# P01-Power.net
KiCad netlist of a schematic drawn in Altium Designer
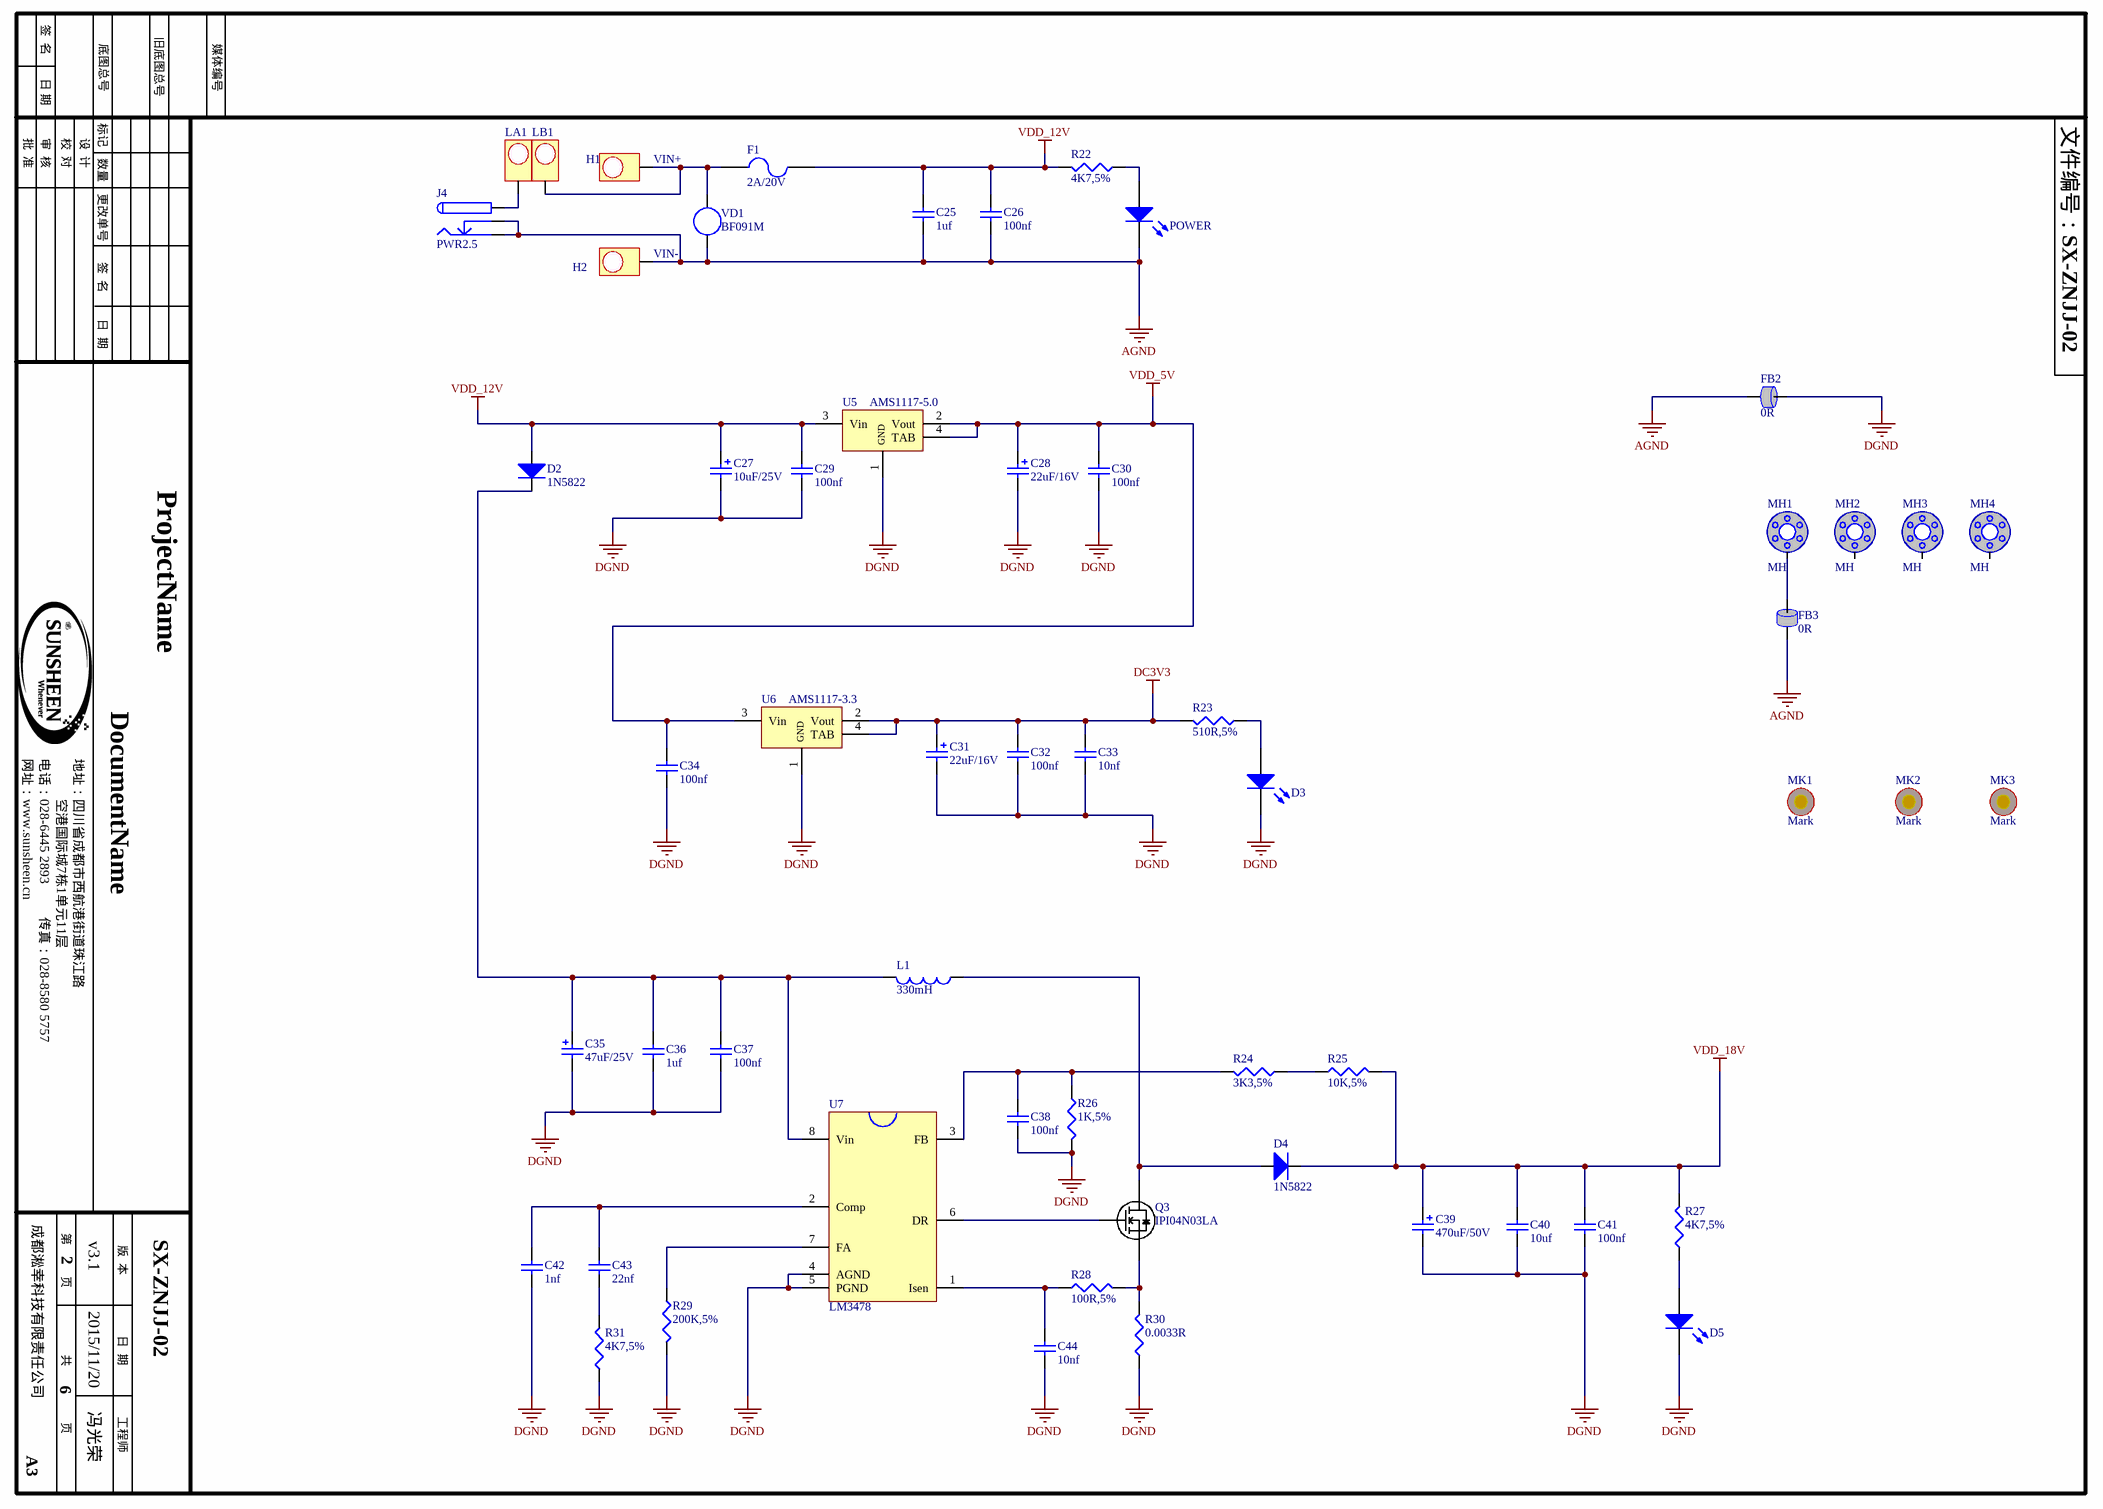
[diagram p0: P01-Power.SchDoc]

(export (version "E")
  (design (tool "Eeschema 10.0.6"))
  (components
    (comp (ref "C25")
      (value "1uf")
      (footprint "Cap0603")
      (description "无极性电容（表贴）")
      (libsource (lib "MyAD_Library") (part "Cap Semi"))
    )
    (comp (ref "C26")
      (value "100nf")
      (footprint "Cap0603")
      (description "无极性电容（表贴）")
      (libsource (lib "MyAD_Library") (part "Cap Semi"))
    )
    (comp (ref "C27")
      (value "10uF/25V")
      (footprint "CapPol1_D5")
      (description "极性电容（径向）")
      (libsource (lib "MyAD_Library") (part "Cap Pol1"))
    )
    (comp (ref "C28")
      (value "22uF/16V")
      (footprint "CapPol1_D5")
      (description "极性电容（径向）")
      (libsource (lib "MyAD_Library") (part "Cap Pol1"))
    )
    (comp (ref "C29")
      (value "100nf")
      (footprint "Cap0603")
      (description "无极性电容（表贴）")
      (libsource (lib "MyAD_Library") (part "Cap Semi"))
    )
    (comp (ref "C30")
      (value "100nf")
      (footprint "Cap0603")
      (description "无极性电容（表贴）")
      (libsource (lib "MyAD_Library") (part "Cap Semi"))
    )
    (comp (ref "C31")
      (value "22uF/16V")
      (footprint "CapPol1_D5")
      (description "极性电容（径向）")
      (libsource (lib "MyAD_Library") (part "Cap Pol1"))
    )
    (comp (ref "C32")
      (value "100nf")
      (footprint "Cap0603")
      (description "无极性电容（表贴）")
      (libsource (lib "MyAD_Library") (part "Cap Semi"))
    )
    (comp (ref "C33")
      (value "10nf")
      (footprint "Cap0603")
      (description "无极性电容（表贴）")
      (libsource (lib "MyAD_Library") (part "Cap Semi"))
    )
    (comp (ref "C34")
      (value "100nf")
      (footprint "Cap0603")
      (description "无极性电容（表贴）")
      (libsource (lib "MyAD_Library") (part "Cap Semi"))
    )
    (comp (ref "C35")
      (value "47uF/25V")
      (footprint "CapPol1_D6")
      (description "极性电容（径向）")
      (libsource (lib "MyAD_Library") (part "Cap Pol1"))
    )
    (comp (ref "C36")
      (value "1uf")
      (footprint "Cap0603")
      (description "无极性电容（表贴）")
      (libsource (lib "MyAD_Library") (part "Cap Semi"))
    )
    (comp (ref "C37")
      (value "100nf")
      (footprint "Cap0603")
      (description "无极性电容（表贴）")
      (libsource (lib "MyAD_Library") (part "Cap Semi"))
    )
    (comp (ref "C38")
      (value "100nf")
      (footprint "Cap0603")
      (description "无极性电容（表贴）")
      (libsource (lib "MyAD_Library") (part "Cap Semi"))
    )
    (comp (ref "C39")
      (value "470uF/50V")
      (footprint "CapPol1_D10")
      (description "极性电容（径向）")
      (libsource (lib "MyAD_Library") (part "Cap Pol1"))
    )
    (comp (ref "C40")
      (value "10uf")
      (footprint "Cap0603")
      (description "无极性电容（表贴）")
      (libsource (lib "MyAD_Library") (part "Cap Semi"))
    )
    (comp (ref "C41")
      (value "100nf")
      (footprint "Cap0603")
      (description "无极性电容（表贴）")
      (libsource (lib "MyAD_Library") (part "Cap Semi"))
    )
    (comp (ref "C42")
      (value "1nf")
      (footprint "Cap0603")
      (description "无极性电容（表贴）")
      (libsource (lib "MyAD_Library") (part "Cap Semi"))
    )
    (comp (ref "C43")
      (value "22nf")
      (footprint "Cap0603")
      (description "无极性电容（表贴）")
      (libsource (lib "MyAD_Library") (part "Cap Semi"))
    )
    (comp (ref "C44")
      (value "10nf")
      (footprint "Cap0603")
      (description "无极性电容（表贴）")
      (libsource (lib "MyAD_Library") (part "Cap Semi"))
    )
    (comp (ref "D2")
      (value "1N5822")
      (footprint "1N5822")
      (description "肖基特二极管")
      (libsource (lib "Schlib1") (part "DIODE"))
    )
    (comp (ref "D3")
      (value "RED")
      (footprint "LED0603")
      (description "Typical RED, GREEN, YELLOW, AMBER GaAs LED")
      (libsource (lib "MyAD_Library") (part "LED"))
    )
    (comp (ref "D4")
      (value "1N5822")
      (footprint "1N5822")
      (description "肖基特二极管")
      (libsource (lib "Schlib1") (part "DIODE"))
    )
    (comp (ref "D5")
      (value "RED")
      (footprint "LED0603")
      (description "Typical RED, GREEN, YELLOW, AMBER GaAs LED")
      (libsource (lib "MyAD_Library") (part "LED"))
    )
    (comp (ref "F1")
      (value "2A/20V")
      (footprint "1812")
      (description "保险丝")
      (libsource (lib "MyAD_Library") (part "Fuse"))
    )
    (comp (ref "FB2")
      (value "0R")
      (footprint "FB0603")
      (description "磁珠")
      (libsource (lib "MyAD_Library") (part "FerriteBead"))
    )
    (comp (ref "FB3")
      (value "0R")
      (footprint "FB0603")
      (description "磁珠")
      (libsource (lib "") (part "FerriteBead_1"))
    )
    (comp (ref "H1")
      (value "VIN+")
      (footprint "HOLE_POWER")
      (description "电源接线孔")
      (libsource (lib "") (part "HOLE_POWER_1"))
    )
    (comp (ref "H2")
      (value "VIN-")
      (footprint "HOLE_POWER")
      (description "电源接线孔")
      (libsource (lib "") (part "HOLE_POWER_1"))
    )
    (comp (ref "J4")
      (value "PWR2.5")
      (footprint "KLD-0202")
      (description "低电压电源连接器")
      (libsource (lib "MyAD_Library") (part "PWR2.5"))
    )
    (comp (ref "L1")
      (value "330mH")
      (footprint "Inductor_12x12x7")
      (description "电感")
      (libsource (lib "Schlib1") (part "Inductor"))
    )
    (comp (ref "LA1")
      (value "HOLE_POWER")
      (footprint "HOLE_POWER")
      (description "电源接线孔")
      (libsource (lib "MyAD_Library") (part "HOLE_POWER"))
    )
    (comp (ref "LB1")
      (value "HOLE_POWER")
      (footprint "HOLE_POWER")
      (description "电源接线孔")
      (libsource (lib "MyAD_Library") (part "HOLE_POWER"))
    )
    (comp (ref "MH1")
      (value "MH")
      (footprint "AS_D3mm-6mm")
      (description "固定孔")
      (libsource (lib "MyAD_Library") (part "MH"))
    )
    (comp (ref "MH2")
      (value "MH")
      (footprint "AS_D3mm-6mm")
      (description "固定孔")
      (libsource (lib "MyAD_Library") (part "MH"))
    )
    (comp (ref "MH3")
      (value "MH")
      (footprint "AS_D3mm-6mm")
      (description "固定孔")
      (libsource (lib "MyAD_Library") (part "MH"))
    )
    (comp (ref "MH4")
      (value "MH")
      (footprint "AS_D3mm-6mm")
      (description "固定孔")
      (libsource (lib "MyAD_Library") (part "MH"))
    )
    (comp (ref "MK1")
      (value "Mark")
      (footprint "MK")
      (description "贴片马克点")
      (libsource (lib "MyAD_Library") (part "Mark"))
    )
    (comp (ref "MK2")
      (value "Mark")
      (footprint "MK")
      (description "贴片马克点")
      (libsource (lib "MyAD_Library") (part "Mark"))
    )
    (comp (ref "MK3")
      (value "Mark")
      (footprint "MK")
      (description "贴片马克点")
      (libsource (lib "MyAD_Library") (part "Mark"))
    )
    (comp (ref "POWER")
      (value "RED")
      (footprint "LED0603")
      (description "Typical RED, GREEN, YELLOW, AMBER GaAs LED")
      (libsource (lib "MyAD_Library") (part "LED"))
    )
    (comp (ref "Q3")
      (value "IPI04N03LA")
      (footprint "TO228")
      (description "N沟道MOS管")
      (libsource (lib "Schlib1") (part "IPI04N03LA"))
    )
    (comp (ref "R22")
      (value "4K7,5%")
      (footprint "Res0603")
      (description "电阻")
      (libsource (lib "MyAD_Library") (part "Res"))
    )
    (comp (ref "R23")
      (value "510R,5%")
      (footprint "Res0603")
      (description "电阻")
      (libsource (lib "MyAD_Library") (part "Res"))
    )
    (comp (ref "R24")
      (value "3K3,5%")
      (footprint "Res0603")
      (description "电阻")
      (libsource (lib "MyAD_Library") (part "Res"))
    )
    (comp (ref "R25")
      (value "10K,5%")
      (footprint "Res0603")
      (description "电阻")
      (libsource (lib "MyAD_Library") (part "Res"))
    )
    (comp (ref "R26")
      (value "1K,5%")
      (footprint "Res0603")
      (description "电阻")
      (libsource (lib "MyAD_Library") (part "Res"))
    )
    (comp (ref "R27")
      (value "4K7,5%")
      (footprint "Res0603")
      (description "电阻")
      (libsource (lib "MyAD_Library") (part "Res"))
    )
    (comp (ref "R28")
      (value "100R,5%")
      (footprint "Res0603")
      (description "电阻")
      (libsource (lib "MyAD_Library") (part "Res"))
    )
    (comp (ref "R29")
      (value "200K,5%")
      (footprint "Res0603")
      (description "电阻")
      (libsource (lib "MyAD_Library") (part "Res"))
    )
    (comp (ref "R30")
      (value "0.0033R")
      (footprint "1206A")
      (description "电阻")
      (libsource (lib "MyAD_Library") (part "Res"))
    )
    (comp (ref "R31")
      (value "4K7,5%")
      (footprint "Res0603")
      (description "电阻")
      (libsource (lib "MyAD_Library") (part "Res"))
    )
    (comp (ref "U5")
      (value "AMS1117-5.0")
      (footprint "AMS1117")
      (description "稳压器")
      (libsource (lib "MyAD_Library") (part "AMS1117-3.3"))
    )
    (comp (ref "U6")
      (value "AMS1117-3.3")
      (footprint "AMS1117")
      (description "稳压器")
      (libsource (lib "MyAD_Library") (part "AMS1117-3.3"))
    )
    (comp (ref "U7")
      (value "LM3478")
      (footprint "SOP65P490X110-8N")
      (libsource (lib "Schlib1") (part "LM3478"))
    )
    (comp (ref "VD1") (value "BF091M") (footprint "B3D230L") (libsource (lib "Schlib1") (part "B3D230L")))
  )
  (nets
    (net (code "1") (name "AGND") (class "Default")
      (node (ref "C25") (pin "1") (pinfunction "1_1") (pintype "passive"))
      (node (ref "C26") (pin "1") (pinfunction "1_1") (pintype "passive"))
      (node (ref "FB2") (pin "1") (pinfunction "1_1") (pintype "passive"))
      (node (ref "FB3") (pin "1") (pinfunction "1_1") (pintype "passive"))
      (node (ref "H2") (pin "1") (pinfunction "1_1") (pintype "passive"))
      (node (ref "J4") (pin "2") (pinfunction "2_2") (pintype "power_in"))
      (node (ref "J4") (pin "3") (pinfunction "3_3") (pintype "power_in"))
      (node (ref "POWER") (pin "K") (pinfunction "K_K") (pintype "passive"))
      (node (ref "VD1") (pin "2") (pinfunction "2_2") (pintype "passive"))
    )
    (net (code "2") (name "DC3V3") (class "Default")
      (node (ref "C31") (pin "1") (pinfunction "1_1") (pintype "passive"))
      (node (ref "C32") (pin "2") (pinfunction "2_2") (pintype "passive"))
      (node (ref "C33") (pin "2") (pinfunction "2_2") (pintype "passive"))
      (node (ref "R23") (pin "2") (pinfunction "2_2") (pintype "passive"))
      (node (ref "U6") (pin "2") (pinfunction "Vout_2") (pintype "passive"))
      (node (ref "U6") (pin "4") (pinfunction "TAB_4") (pintype "passive"))
    )
    (net (code "3") (name "DGND") (class "Default")
      (node (ref "C27") (pin "2") (pinfunction "2_2") (pintype "passive"))
      (node (ref "C28") (pin "2") (pinfunction "2_2") (pintype "passive"))
      (node (ref "C29") (pin "1") (pinfunction "1_1") (pintype "passive"))
      (node (ref "C30") (pin "1") (pinfunction "1_1") (pintype "passive"))
      (node (ref "C31") (pin "2") (pinfunction "2_2") (pintype "passive"))
      (node (ref "C32") (pin "1") (pinfunction "1_1") (pintype "passive"))
      (node (ref "C33") (pin "1") (pinfunction "1_1") (pintype "passive"))
      (node (ref "C34") (pin "1") (pinfunction "1_1") (pintype "passive"))
      (node (ref "C35") (pin "2") (pinfunction "2_2") (pintype "passive"))
      (node (ref "C36") (pin "1") (pinfunction "1_1") (pintype "passive"))
      (node (ref "C37") (pin "1") (pinfunction "1_1") (pintype "passive"))
      (node (ref "C38") (pin "1") (pinfunction "1_1") (pintype "passive"))
      (node (ref "C39") (pin "2") (pinfunction "2_2") (pintype "passive"))
      (node (ref "C40") (pin "1") (pinfunction "1_1") (pintype "passive"))
      (node (ref "C41") (pin "1") (pinfunction "1_1") (pintype "passive"))
      (node (ref "C42") (pin "1") (pinfunction "1_1") (pintype "passive"))
      (node (ref "C44") (pin "1") (pinfunction "1_1") (pintype "passive"))
      (node (ref "D3") (pin "K") (pinfunction "K_K") (pintype "passive"))
      (node (ref "D5") (pin "K") (pinfunction "K_K") (pintype "passive"))
      (node (ref "FB2") (pin "2") (pinfunction "2_2") (pintype "passive"))
      (node (ref "R26") (pin "2") (pinfunction "2_2") (pintype "passive"))
      (node (ref "R29") (pin "1") (pinfunction "1_1") (pintype "passive"))
      (node (ref "R30") (pin "1") (pinfunction "1_1") (pintype "passive"))
      (node (ref "R31") (pin "1") (pinfunction "1_1") (pintype "passive"))
      (node (ref "U5") (pin "1") (pinfunction "GND_1") (pintype "passive"))
      (node (ref "U6") (pin "1") (pinfunction "GND_1") (pintype "passive"))
      (node (ref "U7") (pin "4") (pinfunction "AGND_4") (pintype "passive"))
      (node (ref "U7") (pin "5") (pinfunction "PGND_5") (pintype "passive"))
    )
    (net (code "4") (name "Net-(C43-Pad1)") (class "Default")
      (node (ref "C43") (pin "1") (pinfunction "1_1") (pintype "passive"))
      (node (ref "R31") (pin "2") (pinfunction "2_2") (pintype "passive"))
    )
    (net (code "5") (name "Net-(D3-PadA)") (class "Default")
      (node (ref "D3") (pin "A") (pinfunction "A_A") (pintype "passive"))
      (node (ref "R23") (pin "1") (pinfunction "1_1") (pintype "passive"))
    )
    (net (code "6") (name "Net-(D5-PadA)") (class "Default")
      (node (ref "D5") (pin "A") (pinfunction "A_A") (pintype "passive"))
      (node (ref "R27") (pin "1") (pinfunction "1_1") (pintype "passive"))
    )
    (net (code "7") (name "Net-(F1-Pad1)") (class "Default")
      (node (ref "F1") (pin "1") (pinfunction "1_1") (pintype "passive"))
      (node (ref "H1") (pin "1") (pinfunction "1_1") (pintype "passive"))
      (node (ref "LB1") (pin "1") (pinfunction "1_1") (pintype "passive"))
      (node (ref "VD1") (pin "1") (pinfunction "1_1") (pintype "passive"))
    )
    (net (code "8") (name "Net-(FB3-Pad2)") (class "Default")
      (node (ref "FB3") (pin "2") (pinfunction "2_2") (pintype "passive"))
      (node (ref "MH1") (pin "MH1") (pinfunction "MH1_MH1") (pintype "passive"))
    )
    (net (code "9") (name "Net-(J4-Pad4)") (class "Default")
      (node (ref "J4") (pin "4") (pinfunction "4_4") (pintype "power_in"))
      (node (ref "LA1") (pin "1") (pinfunction "1_1") (pintype "passive"))
    )
    (net (code "10") (name "Net-(POWER-PadA)") (class "Default")
      (node (ref "POWER") (pin "A") (pinfunction "A_A") (pintype "passive"))
      (node (ref "R22") (pin "1") (pinfunction "1_1") (pintype "passive"))
    )
    (net (code "11") (name "Net-(Q3-D)") (class "Default")
      (node (ref "D4") (pin "A") (pinfunction "A_A") (pintype "passive"))
      (node (ref "L1") (pin "2") (pinfunction "2_2") (pintype "passive"))
      (node (ref "Q3") (pin "2") (pinfunction "D_2") (pintype "passive"))
    )
    (net (code "12") (name "Net-(Q3-G)") (class "Default")
      (node (ref "Q3") (pin "1") (pinfunction "G_1") (pintype "passive"))
      (node (ref "U7") (pin "6") (pinfunction "DR_6") (pintype "passive"))
    )
    (net (code "13") (name "Net-(Q3-S)") (class "Default")
      (node (ref "Q3") (pin "3") (pinfunction "S_3") (pintype "passive"))
      (node (ref "R28") (pin "2") (pinfunction "2_2") (pintype "passive"))
      (node (ref "R30") (pin "2") (pinfunction "2_2") (pintype "passive"))
    )
    (net (code "14") (name "Net-(R24-Pad1)") (class "Default")
      (node (ref "R24") (pin "1") (pinfunction "1_1") (pintype "passive"))
      (node (ref "R25") (pin "1") (pinfunction "1_1") (pintype "passive"))
    )
    (net (code "15") (name "Net-(U7-Comp)") (class "Default")
      (node (ref "C42") (pin "2") (pinfunction "2_2") (pintype "passive"))
      (node (ref "C43") (pin "2") (pinfunction "2_2") (pintype "passive"))
      (node (ref "U7") (pin "2") (pinfunction "Comp_2") (pintype "passive"))
    )
    (net (code "16") (name "Net-(U7-FA)") (class "Default")
      (node (ref "R29") (pin "2") (pinfunction "2_2") (pintype "passive"))
      (node (ref "U7") (pin "7") (pinfunction "FA_7") (pintype "passive"))
    )
    (net (code "17") (name "Net-(U7-FB)") (class "Default")
      (node (ref "C38") (pin "2") (pinfunction "2_2") (pintype "passive"))
      (node (ref "R24") (pin "2") (pinfunction "2_2") (pintype "passive"))
      (node (ref "R26") (pin "1") (pinfunction "1_1") (pintype "passive"))
      (node (ref "U7") (pin "3") (pinfunction "FB_3") (pintype "passive"))
    )
    (net (code "18") (name "Net-(U7-Isen)") (class "Default")
      (node (ref "C44") (pin "2") (pinfunction "2_2") (pintype "passive"))
      (node (ref "R28") (pin "1") (pinfunction "1_1") (pintype "passive"))
      (node (ref "U7") (pin "1") (pinfunction "Isen_1") (pintype "passive"))
    )
    (net (code "19") (name "Net-(U7-Vin)") (class "Default")
      (node (ref "C35") (pin "1") (pinfunction "1_1") (pintype "passive"))
      (node (ref "C36") (pin "2") (pinfunction "2_2") (pintype "passive"))
      (node (ref "C37") (pin "2") (pinfunction "2_2") (pintype "passive"))
      (node (ref "D2") (pin "C") (pinfunction "C_C") (pintype "passive"))
      (node (ref "L1") (pin "1") (pinfunction "1_1") (pintype "passive"))
      (node (ref "U7") (pin "8") (pinfunction "Vin_8") (pintype "passive"))
    )
    (net (code "20") (name "VDD_5V") (class "Default")
      (node (ref "C28") (pin "1") (pinfunction "1_1") (pintype "passive"))
      (node (ref "C30") (pin "2") (pinfunction "2_2") (pintype "passive"))
      (node (ref "C34") (pin "2") (pinfunction "2_2") (pintype "passive"))
      (node (ref "U5") (pin "2") (pinfunction "Vout_2") (pintype "passive"))
      (node (ref "U5") (pin "4") (pinfunction "TAB_4") (pintype "passive"))
      (node (ref "U6") (pin "3") (pinfunction "Vin_3") (pintype "passive"))
    )
    (net (code "21") (name "VDD_12V") (class "Default")
      (node (ref "C25") (pin "2") (pinfunction "2_2") (pintype "passive"))
      (node (ref "C26") (pin "2") (pinfunction "2_2") (pintype "passive"))
      (node (ref "C27") (pin "1") (pinfunction "1_1") (pintype "passive"))
      (node (ref "C29") (pin "2") (pinfunction "2_2") (pintype "passive"))
      (node (ref "D2") (pin "A") (pinfunction "A_A") (pintype "passive"))
      (node (ref "F1") (pin "2") (pinfunction "2_2") (pintype "passive"))
      (node (ref "R22") (pin "2") (pinfunction "2_2") (pintype "passive"))
      (node (ref "U5") (pin "3") (pinfunction "Vin_3") (pintype "passive"))
    )
    (net (code "22") (name "VDD_18V") (class "Default")
      (node (ref "C39") (pin "1") (pinfunction "1_1") (pintype "passive"))
      (node (ref "C40") (pin "2") (pinfunction "2_2") (pintype "passive"))
      (node (ref "C41") (pin "2") (pinfunction "2_2") (pintype "passive"))
      (node (ref "D4") (pin "C") (pinfunction "C_C") (pintype "passive"))
      (node (ref "R25") (pin "2") (pinfunction "2_2") (pintype "passive"))
      (node (ref "R27") (pin "2") (pinfunction "2_2") (pintype "passive"))
    )
    (net (code "23") (name "unconnected-(MH2-PadMH1)") (class "Default")
      (node (ref "MH2") (pin "MH1") (pinfunction "MH1_MH1") (pintype "passive"))
    )
    (net (code "24") (name "unconnected-(MH3-PadMH1)") (class "Default")
      (node (ref "MH3") (pin "MH1") (pinfunction "MH1_MH1") (pintype "passive"))
    )
    (net (code "25") (name "unconnected-(MH4-PadMH1)") (class "Default")
      (node (ref "MH4") (pin "MH1") (pinfunction "MH1_MH1") (pintype "passive"))
    )
  )
)
